# auido.net
KiCad netlist of a schematic drawn in Altium Designer
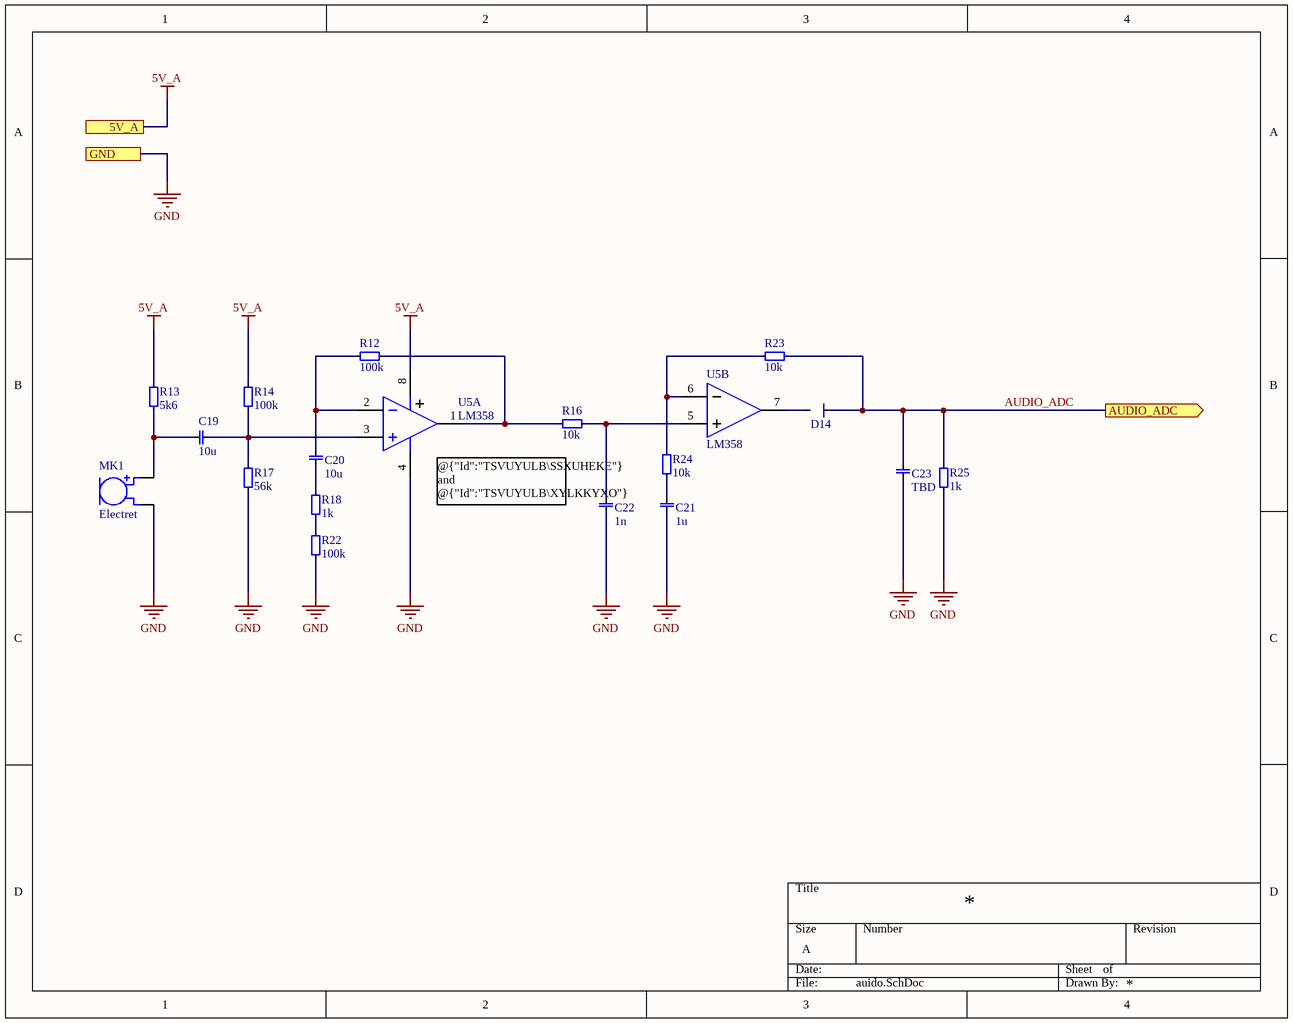
[diagram p0: auido.SchDoc]

(export (version "E")
  (design (tool "Eeschema 10.0.6"))
  (components
    (comp (ref "C19")
      (value "10u")
      (footprint "0603 cap")
      (fields (field (name "Comment") "0603, capacitor"))
      (libsource (lib "jclib") (part "0603, capacitor"))
    )
    (comp (ref "C20")
      (value "10u")
      (footprint "0603 cap")
      (fields (field (name "Comment") "0603, capacitor"))
      (libsource (lib "jclib") (part "0603, capacitor"))
    )
    (comp (ref "C21")
      (value "1u")
      (footprint "0603 cap")
      (fields (field (name "Comment") "0603, capacitor"))
      (libsource (lib "jclib") (part "0603, capacitor"))
    )
    (comp (ref "C22")
      (value "1n")
      (footprint "0603 cap")
      (fields (field (name "Comment") "0603, capacitor"))
      (libsource (lib "jclib") (part "0603, capacitor"))
    )
    (comp (ref "C23")
      (value "TBD")
      (footprint "0603 cap")
      (fields (field (name "Comment") "0603, capacitor"))
      (libsource (lib "jclib") (part "0603, capacitor"))
    )
    (comp (ref "D14") (value "Diode, SMD") (footprint "SOD323") (libsource (lib "jclib") (part "Diode, SMD")))
    (comp (ref "MK1")
      (value "Electret")
      (footprint "ElectretMic_9.7mm_6.7mm")
      (description "D9.7mm H6.7mm, Electrokit art nr: 40290007")
      (libsource (lib "jclib") (part "Electret Mic"))
    )
    (comp (ref "R12")
      (value "100k")
      (footprint "0603")
      (fields (field (name "Comment") "0603, resistor"))
      (libsource (lib "jclib") (part "0603, resistor"))
    )
    (comp (ref "R13")
      (value "5k6")
      (footprint "0603")
      (fields (field (name "Comment") "0603, resistor"))
      (libsource (lib "jclib") (part "0603, resistor"))
    )
    (comp (ref "R14")
      (value "100k")
      (footprint "0603")
      (fields (field (name "Comment") "0603, resistor"))
      (libsource (lib "jclib") (part "0603, resistor"))
    )
    (comp (ref "R16")
      (value "10k")
      (footprint "0603")
      (fields (field (name "Comment") "0603, resistor"))
      (libsource (lib "jclib") (part "0603, resistor"))
    )
    (comp (ref "R17")
      (value "56k")
      (footprint "0603")
      (fields (field (name "Comment") "0603, resistor"))
      (libsource (lib "jclib") (part "0603, resistor"))
    )
    (comp (ref "R18")
      (value "1k")
      (footprint "0603")
      (fields (field (name "Comment") "0603, resistor"))
      (libsource (lib "jclib") (part "0603, resistor"))
    )
    (comp (ref "R22")
      (value "100k")
      (footprint "0603")
      (fields (field (name "Comment") "0603, resistor"))
      (libsource (lib "jclib") (part "0603, resistor"))
    )
    (comp (ref "R23")
      (value "10k")
      (footprint "0603")
      (fields (field (name "Comment") "0603, resistor"))
      (libsource (lib "jclib") (part "0603, resistor"))
    )
    (comp (ref "R24")
      (value "10k")
      (footprint "0603")
      (fields (field (name "Comment") "0603, resistor"))
      (libsource (lib "jclib") (part "0603, resistor"))
    )
    (comp (ref "R25")
      (value "1k")
      (footprint "0603")
      (fields (field (name "Comment") "0603, resistor"))
      (libsource (lib "jclib") (part "0603, resistor"))
    )
    (comp (ref "U5")
      (value "LM358")
      (footprint "SOIC8")
      (description "Dual FET-Input Operational Amplifier")
      (fields (field (name "PART NUMBER") "LM358P"))
      (libsource (lib "jclib") (part "LM358"))
    )
  )
  (nets
    (net (code "1") (name "/AUDIO_ADC") (class "Default")
      (node (ref "C23") (pin "0") (pinfunction "0_0") (pintype "passive"))
      (node (ref "D14") (pin "1") (pinfunction "1_1") (pintype "passive"))
      (node (ref "R23") (pin "1") (pinfunction "1_1") (pintype "passive"))
      (node (ref "R25") (pin "0") (pinfunction "0_0") (pintype "passive"))
    )
    (net (code "2") (name "5V_A") (class "Default")
      (node (ref "R13") (pin "0") (pinfunction "0_0") (pintype "passive"))
      (node (ref "R14") (pin "0") (pinfunction "0_0") (pintype "passive"))
      (node (ref "U5") (pin "8") (pinfunction "V+_8") (pintype "power_in"))
    )
    (net (code "3") (name "GND") (class "Default")
      (node (ref "C21") (pin "0") (pinfunction "0_0") (pintype "passive"))
      (node (ref "C22") (pin "0") (pinfunction "0_0") (pintype "passive"))
      (node (ref "C23") (pin "1") (pinfunction "1_1") (pintype "passive"))
      (node (ref "MK1") (pin "2") (pinfunction "2_2") (pintype "passive"))
      (node (ref "R17") (pin "1") (pinfunction "1_1") (pintype "passive"))
      (node (ref "R22") (pin "1") (pinfunction "1_1") (pintype "passive"))
      (node (ref "R25") (pin "1") (pinfunction "1_1") (pintype "passive"))
      (node (ref "U5") (pin "4") (pinfunction "V-_4") (pintype "power_in"))
    )
    (net (code "4") (name "Net-(C19-Pad1)") (class "Default")
      (node (ref "C19") (pin "1") (pinfunction "1_1") (pintype "passive"))
      (node (ref "MK1") (pin "1") (pinfunction "1_1") (pintype "passive"))
      (node (ref "R13") (pin "1") (pinfunction "1_1") (pintype "passive"))
    )
    (net (code "5") (name "Net-(C20-Pad0)") (class "Default")
      (node (ref "C20") (pin "0") (pinfunction "0_0") (pintype "passive"))
      (node (ref "R18") (pin "0") (pinfunction "0_0") (pintype "passive"))
    )
    (net (code "6") (name "Net-(C21-Pad1)") (class "Default")
      (node (ref "C21") (pin "1") (pinfunction "1_1") (pintype "passive"))
      (node (ref "R24") (pin "1") (pinfunction "1_1") (pintype "passive"))
    )
    (net (code "7") (name "Net-(R18-Pad1)") (class "Default")
      (node (ref "R18") (pin "1") (pinfunction "1_1") (pintype "passive"))
      (node (ref "R22") (pin "0") (pinfunction "0_0") (pintype "passive"))
    )
    (net (code "8") (name "Net-(U5A-IN+)") (class "Default")
      (node (ref "C19") (pin "0") (pinfunction "0_0") (pintype "passive"))
      (node (ref "R14") (pin "1") (pinfunction "1_1") (pintype "passive"))
      (node (ref "R17") (pin "0") (pinfunction "0_0") (pintype "passive"))
      (node (ref "U5") (pin "3") (pinfunction "IN+_3") (pintype "passive"))
    )
    (net (code "9") (name "Net-(U5A-IN-)") (class "Default")
      (node (ref "C20") (pin "1") (pinfunction "1_1") (pintype "passive"))
      (node (ref "R12") (pin "0") (pinfunction "0_0") (pintype "passive"))
      (node (ref "U5") (pin "2") (pinfunction "IN-_2") (pintype "passive"))
    )
    (net (code "10") (name "Net-(U5A-OUT1)") (class "Default")
      (node (ref "R12") (pin "1") (pinfunction "1_1") (pintype "passive"))
      (node (ref "R16") (pin "0") (pinfunction "0_0") (pintype "passive"))
      (node (ref "U5") (pin "1") (pinfunction "OUT1_1") (pintype "passive"))
    )
    (net (code "11") (name "Net-(U5B-IN+)") (class "Default")
      (node (ref "C22") (pin "1") (pinfunction "1_1") (pintype "passive"))
      (node (ref "R16") (pin "1") (pinfunction "1_1") (pintype "passive"))
      (node (ref "U5") (pin "5") (pinfunction "IN+_5") (pintype "passive"))
    )
    (net (code "12") (name "Net-(U5B-IN-)") (class "Default")
      (node (ref "R23") (pin "0") (pinfunction "0_0") (pintype "passive"))
      (node (ref "R24") (pin "0") (pinfunction "0_0") (pintype "passive"))
      (node (ref "U5") (pin "6") (pinfunction "IN-_6") (pintype "passive"))
    )
    (net (code "13") (name "Net-(U5B-OUT2)") (class "Default")
      (node (ref "D14") (pin "2") (pinfunction "2_2") (pintype "passive"))
      (node (ref "U5") (pin "7") (pinfunction "OUT2_7") (pintype "passive"))
    )
  )
)
